# sdr_cutoff.net
KiCad netlist of a schematic drawn in EAGLE
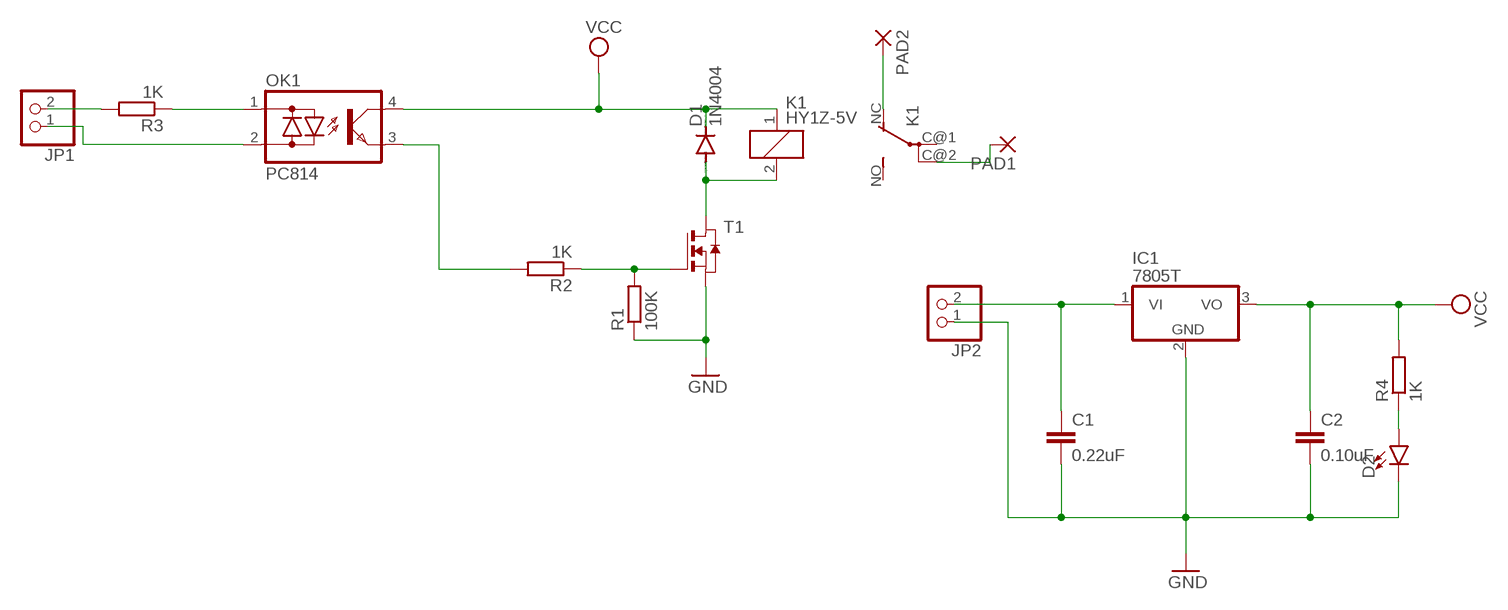
[diagram p0: schematic, sheet 1]

(export (version "E")
  (design (tool "Eeschema 10.0.6"))
  (components
    (comp (ref "C1")
      (value "0.22uF")
      (footprint "eagle-import:C025-024X044")
      (libsource (lib "eagle-import") (part "C-EU025-024X044"))
    )
    (comp (ref "C2")
      (value "0.10uF")
      (footprint "eagle-import:C025-024X044")
      (libsource (lib "eagle-import") (part "C-EU025-024X044"))
    )
    (comp (ref "D1")
      (value "1N4004")
      (footprint "eagle-import:DO41-10")
      (libsource (lib "eagle-import") (part "1N4004"))
    )
    (comp (ref "D2")
      (value "LED3MM")
      (footprint "eagle-import:LED_3MM")
      (libsource (lib "eagle-import") (part "LED3MM"))
    )
    (comp (ref "IC1")
      (value "7805T")
      (footprint "eagle-import:TO220H")
      (libsource (lib "eagle-import") (part "78T05"))
    )
    (comp (ref "JP1")
      (value "PINHD-1X2")
      (footprint "eagle-import:1X02")
      (libsource (lib "eagle-import") (part "PINHD-1X2"))
    )
    (comp (ref "JP2")
      (value "PINHD-1X2")
      (footprint "eagle-import:1X02")
      (libsource (lib "eagle-import") (part "PINHD-1X2"))
    )
    (comp (ref "K1")
      (value "HY1Z-5V")
      (footprint "eagle-import:HY")
      (fields (field (name "MF") "AROMAT/ MATSUSHITA"))
      (libsource (lib "eagle-import") (part "HY1Z-5V"))
    )
    (comp (ref "OK1")
      (value "PC814")
      (footprint "eagle-import:DIL04")
      (libsource (lib "eagle-import") (part "PC814"))
    )
    (comp (ref "PAD1")
      (value "2,54/0,8")
      (footprint "eagle-import:2,54_0,8")
      (libsource (lib "eagle-import") (part "2,54/0,8"))
    )
    (comp (ref "PAD2")
      (value "2,54/0,8")
      (footprint "eagle-import:2,54_0,8")
      (libsource (lib "eagle-import") (part "2,54/0,8"))
    )
    (comp (ref "R1")
      (value "100K")
      (footprint "eagle-import:0204_5")
      (libsource (lib "eagle-import") (part "R-EU_0204/5"))
    )
    (comp (ref "R2")
      (value "1K")
      (footprint "eagle-import:0204_5")
      (libsource (lib "eagle-import") (part "R-EU_0204/5"))
    )
    (comp (ref "R3")
      (value "1K")
      (footprint "eagle-import:0204_5")
      (libsource (lib "eagle-import") (part "R-EU_0204/5"))
    )
    (comp (ref "R4")
      (value "1K")
      (footprint "eagle-import:0204_5")
      (libsource (lib "eagle-import") (part "R-EU_0204/5"))
    )
    (comp (ref "T1")
      (value "NMOSE3L")
      (footprint "eagle-import:E3LINE")
      (libsource (lib "eagle-import") (part "NMOSE3L"))
    )
  )
  (nets
    (net (code "1") (name "GND") (class "Default")
      (node (ref "C1") (pin "2") (pinfunction "2_2") (pintype "passive"))
      (node (ref "C2") (pin "2") (pinfunction "2_2") (pintype "passive"))
      (node (ref "D2") (pin "K") (pinfunction "C_K") (pintype "passive"))
      (node (ref "IC1") (pin "2") (pinfunction "GND_2") (pintype "passive"))
      (node (ref "JP2") (pin "1") (pinfunction "1_1") (pintype "passive"))
      (node (ref "R1") (pin "1") (pinfunction "1_1") (pintype "passive"))
      (node (ref "T1") (pin "3") (pinfunction "S_3") (pintype "passive"))
    )
    (net (code "2") (name "Net-(D2-PadA)") (class "Default")
      (node (ref "D2") (pin "A") (pinfunction "A_A") (pintype "passive"))
      (node (ref "R4") (pin "1") (pinfunction "1_1") (pintype "passive"))
    )
    (net (code "3") (name "Net-(IC1-VI)") (class "Default")
      (node (ref "C1") (pin "1") (pinfunction "1_1") (pintype "passive"))
      (node (ref "IC1") (pin "1") (pinfunction "VI_1") (pintype "input"))
      (node (ref "JP2") (pin "2") (pinfunction "2_2") (pintype "passive"))
    )
    (net (code "4") (name "Net-(JP1-Pad2)") (class "Default")
      (node (ref "JP1") (pin "2") (pinfunction "2_2") (pintype "passive"))
      (node (ref "R3") (pin "2") (pinfunction "2_2") (pintype "passive"))
    )
    (net (code "5") (name "Net-(K1B-O)") (class "Default")
      (node (ref "K1") (pin "NC") (pinfunction "O_NC") (pintype "passive"))
      (node (ref "PAD2") (pin "1") (pinfunction "P_1") (pintype "passive"))
    )
    (net (code "6") (name "Net-(OK1-AC1)") (class "Default")
      (node (ref "OK1") (pin "1") (pinfunction "AC1_1") (pintype "passive"))
      (node (ref "R3") (pin "1") (pinfunction "1_1") (pintype "passive"))
    )
    (net (code "7") (name "Net-(OK1-AC2)") (class "Default")
      (node (ref "JP1") (pin "1") (pinfunction "1_1") (pintype "passive"))
      (node (ref "OK1") (pin "2") (pinfunction "AC2_2") (pintype "passive"))
    )
    (net (code "8") (name "Net-(OK1-E)") (class "Default")
      (node (ref "OK1") (pin "3") (pinfunction "E_3") (pintype "passive"))
      (node (ref "R2") (pin "2") (pinfunction "2_2") (pintype "passive"))
    )
    (net (code "9") (name "Net-(PAD1-P)") (class "Default")
      (node (ref "K1") (pin "C@2") (pinfunction "P_C@2") (pintype "passive"))
      (node (ref "PAD1") (pin "1") (pinfunction "P_1") (pintype "passive"))
    )
    (net (code "10") (name "Net-(T1-D)") (class "Default")
      (node (ref "D1") (pin "A") (pinfunction "A_A") (pintype "passive"))
      (node (ref "K1") (pin "2") (pinfunction "2_2") (pintype "passive"))
      (node (ref "T1") (pin "1") (pinfunction "D_1") (pintype "passive"))
    )
    (net (code "11") (name "Net-(T1-G)") (class "Default")
      (node (ref "R1") (pin "2") (pinfunction "2_2") (pintype "passive"))
      (node (ref "R2") (pin "1") (pinfunction "1_1") (pintype "passive"))
      (node (ref "T1") (pin "2") (pinfunction "G_2") (pintype "passive"))
    )
    (net (code "12") (name "VCC") (class "Default")
      (node (ref "C2") (pin "1") (pinfunction "1_1") (pintype "passive"))
      (node (ref "D1") (pin "C") (pinfunction "C_C") (pintype "passive"))
      (node (ref "IC1") (pin "3") (pinfunction "VO_3") (pintype "passive"))
      (node (ref "K1") (pin "1") (pinfunction "1_1") (pintype "passive"))
      (node (ref "OK1") (pin "4") (pinfunction "C_4") (pintype "passive"))
      (node (ref "R4") (pin "2") (pinfunction "2_2") (pintype "passive"))
    )
    (net (code "13") (name "unconnected-(K1B-P-PadC@1)") (class "Default")
      (node (ref "K1") (pin "C@1") (pinfunction "P_C@1") (pintype "passive"))
    )
    (net (code "14") (name "unconnected-(K1B-S-PadNO)") (class "Default")
      (node (ref "K1") (pin "NO") (pinfunction "S_NO") (pintype "passive"))
    )
  )
)
